# Peripheral.net
KiCad netlist of a schematic drawn in Altium Designer
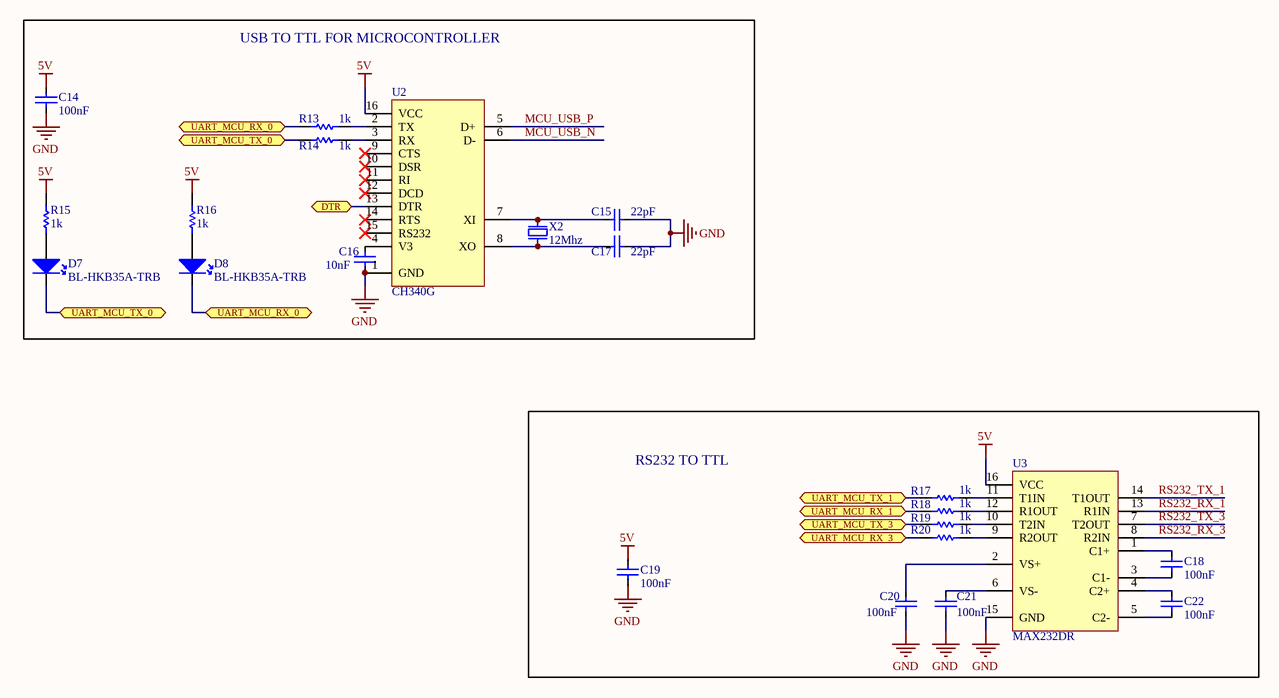
[diagram p0: Peripheral.SchDoc]

(export (version "E")
  (design (tool "Eeschema 10.0.6"))
  (components
    (comp (ref "C14")
      (value "100nF")
      (footprint "CAP-0603")
      (fields
        (field (name "MANUFACTURER") "TDK")
        (field (name "VOLTAGE") "50V")
        (field (name "TOLERANCE") "%10")
      )
      (libsource (lib "My_Libs") (part "CGA3E2X7R1H104K080AA"))
    )
    (comp (ref "C15")
      (value "22pF")
      (footprint "CAP-0805")
      (fields
        (field (name "MANUFACTURER") "Samsung Electro-Mechanics")
        (field (name "VOLTAGE") "50V")
        (field (name "TOLERANCE") "%5")
      )
      (libsource (lib "My_Libs") (part "CL21C220JBANNNC"))
    )
    (comp (ref "C16")
      (value "10nF")
      (footprint "CAP-0603")
      (fields
        (field (name "MANUFACTURER") "AVX")
        (field (name "VOLTAGE") "100V")
        (field (name "TOLERANCE") "%10")
      )
      (libsource (lib "My_Libs") (part "06031C103K4T4A"))
    )
    (comp (ref "C17")
      (value "22pF")
      (footprint "CAP-0805")
      (fields
        (field (name "MANUFACTURER") "Samsung Electro-Mechanics")
        (field (name "VOLTAGE") "50V")
        (field (name "TOLERANCE") "%5")
      )
      (libsource (lib "My_Libs") (part "CL21C220JBANNNC"))
    )
    (comp (ref "C18")
      (value "100nF")
      (footprint "CAP-0603")
      (fields
        (field (name "MANUFACTURER") "TDK")
        (field (name "VOLTAGE") "50V")
        (field (name "TOLERANCE") "%10")
      )
      (libsource (lib "My_Libs") (part "CGA3E2X7R1H104K080AA"))
    )
    (comp (ref "C19")
      (value "100nF")
      (footprint "CAP-0603")
      (fields
        (field (name "MANUFACTURER") "TDK")
        (field (name "VOLTAGE") "50V")
        (field (name "TOLERANCE") "%10")
      )
      (libsource (lib "My_Libs") (part "CGA3E2X7R1H104K080AA"))
    )
    (comp (ref "C20")
      (value "100nF")
      (footprint "CAP-0603")
      (fields
        (field (name "MANUFACTURER") "TDK")
        (field (name "VOLTAGE") "50V")
        (field (name "TOLERANCE") "%10")
      )
      (libsource (lib "My_Libs") (part "CGA3E2X7R1H104K080AA"))
    )
    (comp (ref "C21")
      (value "100nF")
      (footprint "CAP-0603")
      (fields
        (field (name "MANUFACTURER") "TDK")
        (field (name "VOLTAGE") "50V")
        (field (name "TOLERANCE") "%10")
      )
      (libsource (lib "My_Libs") (part "CGA3E2X7R1H104K080AA"))
    )
    (comp (ref "C22")
      (value "100nF")
      (footprint "CAP-0603")
      (fields
        (field (name "MANUFACTURER") "TDK")
        (field (name "VOLTAGE") "50V")
        (field (name "TOLERANCE") "%10")
      )
      (libsource (lib "My_Libs") (part "CGA3E2X7R1H104K080AA"))
    )
    (comp (ref "D7")
      (value "BL-HKB35A-TRB")
      (footprint "LED-0805")
      (fields (field (name "MANUFACTURER") "BRIGHT LED"))
      (libsource (lib "My_Libs") (part "BL-HKB35A-TRB"))
    )
    (comp (ref "D8")
      (value "BL-HKB35A-TRB")
      (footprint "LED-0805")
      (fields (field (name "MANUFACTURER") "BRIGHT LED"))
      (libsource (lib "My_Libs") (part "BL-HKB35A-TRB"))
    )
    (comp (ref "R13")
      (value "1k")
      (footprint "RES-0603")
      (fields
        (field (name "MANUFACTURER") "Vishay")
        (field (name "TOLERANCE") "%1")
        (field (name "POWER") "0.1W")
      )
      (libsource (lib "My_Libs") (part "CRCW06031K00FKEAC"))
    )
    (comp (ref "R14")
      (value "1k")
      (footprint "RES-0603")
      (fields
        (field (name "MANUFACTURER") "Vishay")
        (field (name "TOLERANCE") "%1")
        (field (name "POWER") "0.1W")
      )
      (libsource (lib "My_Libs") (part "CRCW06031K00FKEAC"))
    )
    (comp (ref "R15")
      (value "1k")
      (footprint "RES-0603")
      (fields
        (field (name "MANUFACTURER") "Vishay")
        (field (name "TOLERANCE") "%1")
        (field (name "POWER") "0.1W")
      )
      (libsource (lib "My_Libs") (part "CRCW06031K00FKEAC"))
    )
    (comp (ref "R16")
      (value "1k")
      (footprint "RES-0603")
      (fields
        (field (name "MANUFACTURER") "Vishay")
        (field (name "TOLERANCE") "%1")
        (field (name "POWER") "0.1W")
      )
      (libsource (lib "My_Libs") (part "CRCW06031K00FKEAC"))
    )
    (comp (ref "R17")
      (value "1k")
      (footprint "RES-0603")
      (fields
        (field (name "MANUFACTURER") "Vishay")
        (field (name "TOLERANCE") "%1")
        (field (name "POWER") "0.1W")
      )
      (libsource (lib "My_Libs") (part "CRCW06031K00FKEAC"))
    )
    (comp (ref "R18")
      (value "1k")
      (footprint "RES-0603")
      (fields
        (field (name "MANUFACTURER") "Vishay")
        (field (name "TOLERANCE") "%1")
        (field (name "POWER") "0.1W")
      )
      (libsource (lib "My_Libs") (part "CRCW06031K00FKEAC"))
    )
    (comp (ref "R19")
      (value "1k")
      (footprint "RES-0603")
      (fields
        (field (name "MANUFACTURER") "Vishay")
        (field (name "TOLERANCE") "%1")
        (field (name "POWER") "0.1W")
      )
      (libsource (lib "My_Libs") (part "CRCW06031K00FKEAC"))
    )
    (comp (ref "R20")
      (value "1k")
      (footprint "RES-0603")
      (fields
        (field (name "MANUFACTURER") "Vishay")
        (field (name "TOLERANCE") "%1")
        (field (name "POWER") "0.1W")
      )
      (libsource (lib "My_Libs") (part "CRCW06031K00FKEAC"))
    )
    (comp (ref "U2")
      (value "CH340G")
      (footprint "16-SOIC_CH340G")
      (libsource (lib "My_Libs") (part "CH340G"))
    )
    (comp (ref "U3")
      (value "MAX232DR")
      (footprint "16-SOIC_MAX232DR")
      (fields (field (name "MANUFACTURER") "Texas Instruments"))
      (libsource (lib "My_Libs") (part "MAX232DR"))
    )
    (comp (ref "X2")
      (value "12Mhz")
      (footprint "OSC-THT (11.5*5.00*3.60)")
      (fields (field (name "MANUFACTURER") "ANSEN"))
      (libsource (lib "My_Libs") (part "AS49S-12M-FC160F3"))
    )
  )
  (nets
    (net (code "1") (name "/DTR") (class "Default")
      (node (ref "U2") (pin "13") (pinfunction "DTR_13") (pintype "passive"))
    )
    (net (code "2") (name "/MCU_USB_N") (class "Default")
      (node (ref "U2") (pin "6") (pinfunction "D-_6") (pintype "passive"))
    )
    (net (code "3") (name "/MCU_USB_P") (class "Default")
      (node (ref "U2") (pin "5") (pinfunction "D+_5") (pintype "passive"))
    )
    (net (code "4") (name "/RS232_RX_1") (class "Default")
      (node (ref "U3") (pin "13") (pinfunction "R1IN_13") (pintype "passive"))
    )
    (net (code "5") (name "/RS232_RX_3") (class "Default")
      (node (ref "U3") (pin "8") (pinfunction "R2IN_8") (pintype "passive"))
    )
    (net (code "6") (name "/RS232_TX_1") (class "Default")
      (node (ref "U3") (pin "14") (pinfunction "T1OUT_14") (pintype "passive"))
    )
    (net (code "7") (name "/RS232_TX_3") (class "Default")
      (node (ref "U3") (pin "7") (pinfunction "T2OUT_7") (pintype "passive"))
    )
    (net (code "8") (name "/UART_MCU_RX_0") (class "Default")
      (node (ref "D8") (pin "2") (pinfunction "K_2") (pintype "passive"))
      (node (ref "R13") (pin "2") (pinfunction "2_2") (pintype "passive"))
    )
    (net (code "9") (name "/UART_MCU_RX_1") (class "Default")
      (node (ref "R18") (pin "2") (pinfunction "2_2") (pintype "passive"))
    )
    (net (code "10") (name "/UART_MCU_RX_3") (class "Default")
      (node (ref "R20") (pin "2") (pinfunction "2_2") (pintype "passive"))
    )
    (net (code "11") (name "/UART_MCU_TX_0") (class "Default")
      (node (ref "D7") (pin "2") (pinfunction "K_2") (pintype "passive"))
      (node (ref "R14") (pin "2") (pinfunction "2_2") (pintype "passive"))
    )
    (net (code "12") (name "/UART_MCU_TX_1") (class "Default")
      (node (ref "R17") (pin "2") (pinfunction "2_2") (pintype "passive"))
    )
    (net (code "13") (name "/UART_MCU_TX_3") (class "Default")
      (node (ref "R19") (pin "2") (pinfunction "2_2") (pintype "passive"))
    )
    (net (code "14") (name "5V") (class "Default")
      (node (ref "C14") (pin "2") (pinfunction "2_2") (pintype "passive"))
      (node (ref "C19") (pin "2") (pinfunction "2_2") (pintype "passive"))
      (node (ref "R15") (pin "2") (pinfunction "2_2") (pintype "passive"))
      (node (ref "R16") (pin "2") (pinfunction "2_2") (pintype "passive"))
      (node (ref "U2") (pin "16") (pinfunction "VCC_16") (pintype "passive"))
      (node (ref "U3") (pin "16") (pinfunction "VCC_16") (pintype "passive"))
    )
    (net (code "15") (name "GND") (class "Default")
      (node (ref "C14") (pin "1") (pinfunction "1_1") (pintype "passive"))
      (node (ref "C15") (pin "1") (pinfunction "1_1") (pintype "passive"))
      (node (ref "C16") (pin "1") (pinfunction "1_1") (pintype "passive"))
      (node (ref "C17") (pin "1") (pinfunction "1_1") (pintype "passive"))
      (node (ref "C19") (pin "1") (pinfunction "1_1") (pintype "passive"))
      (node (ref "C20") (pin "1") (pinfunction "1_1") (pintype "passive"))
      (node (ref "C21") (pin "1") (pinfunction "1_1") (pintype "passive"))
      (node (ref "U2") (pin "1") (pinfunction "GND_1") (pintype "passive"))
      (node (ref "U3") (pin "15") (pinfunction "GND_15") (pintype "passive"))
    )
    (net (code "16") (name "Net-(D7-A)") (class "Default")
      (node (ref "D7") (pin "1") (pinfunction "A_1") (pintype "passive"))
      (node (ref "R15") (pin "1") (pinfunction "1_1") (pintype "passive"))
    )
    (net (code "17") (name "Net-(D8-A)") (class "Default")
      (node (ref "D8") (pin "1") (pinfunction "A_1") (pintype "passive"))
      (node (ref "R16") (pin "1") (pinfunction "1_1") (pintype "passive"))
    )
    (net (code "18") (name "Net-(U2-RX)") (class "Default")
      (node (ref "R14") (pin "1") (pinfunction "1_1") (pintype "passive"))
      (node (ref "U2") (pin "3") (pinfunction "RX_3") (pintype "passive"))
    )
    (net (code "19") (name "Net-(U2-TX)") (class "Default")
      (node (ref "R13") (pin "1") (pinfunction "1_1") (pintype "passive"))
      (node (ref "U2") (pin "2") (pinfunction "TX_2") (pintype "passive"))
    )
    (net (code "20") (name "Net-(U2-V3)") (class "Default")
      (node (ref "C16") (pin "2") (pinfunction "2_2") (pintype "passive"))
      (node (ref "U2") (pin "4") (pinfunction "V3_4") (pintype "passive"))
    )
    (net (code "21") (name "Net-(U2-XI)") (class "Default")
      (node (ref "C15") (pin "2") (pinfunction "2_2") (pintype "passive"))
      (node (ref "U2") (pin "7") (pinfunction "XI_7") (pintype "passive"))
      (node (ref "X2") (pin "2") (pinfunction "2_2") (pintype "passive"))
    )
    (net (code "22") (name "Net-(U2-XO)") (class "Default")
      (node (ref "C17") (pin "2") (pinfunction "2_2") (pintype "passive"))
      (node (ref "U2") (pin "8") (pinfunction "XO_8") (pintype "passive"))
      (node (ref "X2") (pin "1") (pinfunction "1_1") (pintype "passive"))
    )
    (net (code "23") (name "Net-(U3-C1+)") (class "Default")
      (node (ref "C18") (pin "2") (pinfunction "2_2") (pintype "passive"))
      (node (ref "U3") (pin "1") (pinfunction "C1+_1") (pintype "passive"))
    )
    (net (code "24") (name "Net-(U3-C1-)") (class "Default")
      (node (ref "C18") (pin "1") (pinfunction "1_1") (pintype "passive"))
      (node (ref "U3") (pin "3") (pinfunction "C1-_3") (pintype "passive"))
    )
    (net (code "25") (name "Net-(U3-C2+)") (class "Default")
      (node (ref "C22") (pin "2") (pinfunction "2_2") (pintype "passive"))
      (node (ref "U3") (pin "4") (pinfunction "C2+_4") (pintype "passive"))
    )
    (net (code "26") (name "Net-(U3-C2-)") (class "Default")
      (node (ref "C22") (pin "1") (pinfunction "1_1") (pintype "passive"))
      (node (ref "U3") (pin "5") (pinfunction "C2-_5") (pintype "passive"))
    )
    (net (code "27") (name "Net-(U3-R1OUT)") (class "Default")
      (node (ref "R18") (pin "1") (pinfunction "1_1") (pintype "passive"))
      (node (ref "U3") (pin "12") (pinfunction "R1OUT_12") (pintype "passive"))
    )
    (net (code "28") (name "Net-(U3-R2OUT)") (class "Default")
      (node (ref "R20") (pin "1") (pinfunction "1_1") (pintype "passive"))
      (node (ref "U3") (pin "9") (pinfunction "R2OUT_9") (pintype "passive"))
    )
    (net (code "29") (name "Net-(U3-T1IN)") (class "Default")
      (node (ref "R17") (pin "1") (pinfunction "1_1") (pintype "passive"))
      (node (ref "U3") (pin "11") (pinfunction "T1IN_11") (pintype "passive"))
    )
    (net (code "30") (name "Net-(U3-T2IN)") (class "Default")
      (node (ref "R19") (pin "1") (pinfunction "1_1") (pintype "passive"))
      (node (ref "U3") (pin "10") (pinfunction "T2IN_10") (pintype "passive"))
    )
    (net (code "31") (name "Net-(U3-VS+)") (class "Default")
      (node (ref "C20") (pin "2") (pinfunction "2_2") (pintype "passive"))
      (node (ref "U3") (pin "2") (pinfunction "VS+_2") (pintype "passive"))
    )
    (net (code "32") (name "Net-(U3-VS-)") (class "Default")
      (node (ref "C21") (pin "2") (pinfunction "2_2") (pintype "passive"))
      (node (ref "U3") (pin "6") (pinfunction "VS-_6") (pintype "passive"))
    )
    (net (code "33") (name "unconnected-(U2-CTS-Pad9)") (class "Default")
      (node (ref "U2") (pin "9") (pinfunction "CTS_9") (pintype "passive+no_connect"))
    )
    (net (code "34") (name "unconnected-(U2-DCD-Pad12)") (class "Default")
      (node (ref "U2") (pin "12") (pinfunction "DCD_12") (pintype "passive+no_connect"))
    )
    (net (code "35") (name "unconnected-(U2-DSR-Pad10)") (class "Default")
      (node (ref "U2") (pin "10") (pinfunction "DSR_10") (pintype "passive+no_connect"))
    )
    (net (code "36") (name "unconnected-(U2-RI-Pad11)") (class "Default")
      (node (ref "U2") (pin "11") (pinfunction "RI_11") (pintype "passive+no_connect"))
    )
    (net (code "37") (name "unconnected-(U2-RS232-Pad15)") (class "Default")
      (node (ref "U2") (pin "15") (pinfunction "RS232_15") (pintype "passive+no_connect"))
    )
    (net (code "38") (name "unconnected-(U2-RTS-Pad14)") (class "Default")
      (node (ref "U2") (pin "14") (pinfunction "RTS_14") (pintype "passive+no_connect"))
    )
  )
)
